# BontempoV2.net
KiCad netlist of a schematic drawn in EAGLE
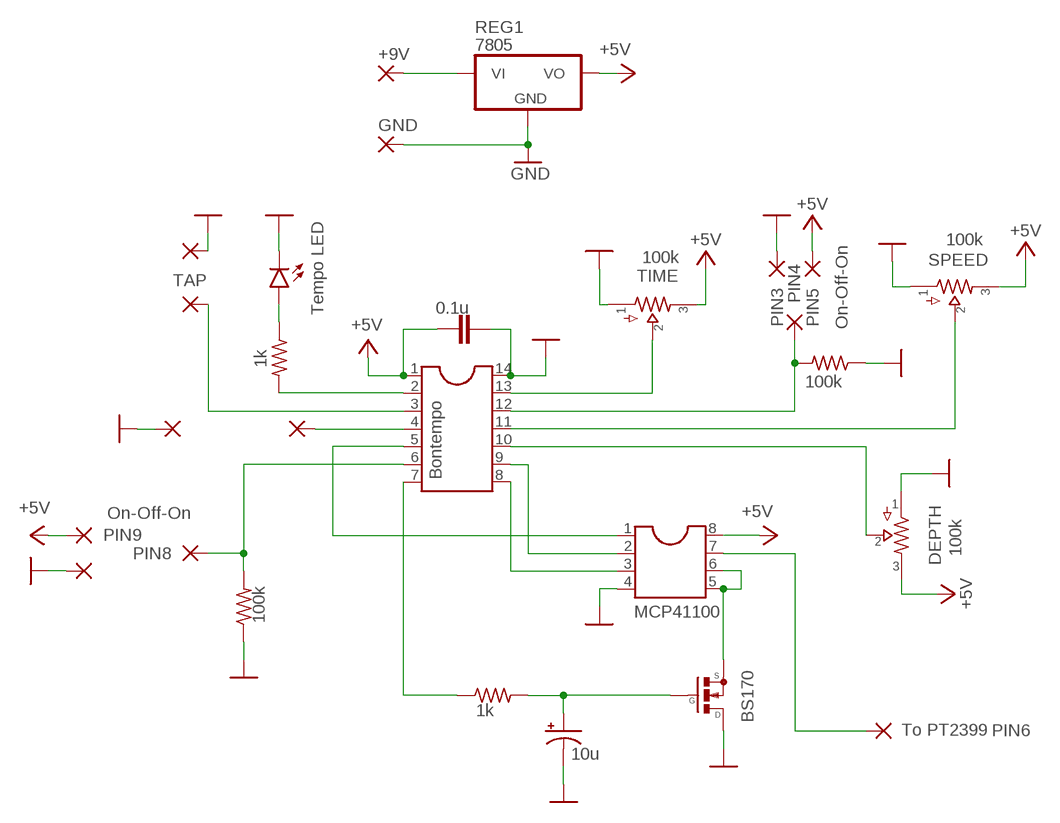
[diagram p0: schematic, sheet 1]

(export (version "E")
  (design (tool "Eeschema 10.0.6"))
  (components
    (comp (ref "+9V")
      (value "2,54/1,1")
      (footprint "eagle-import:2,54_1,1")
      (libsource (lib "eagle-import") (part "2,54/1,1"))
    )
    (comp (ref "C1")
      (value "10u")
      (footprint "eagle-import:050_020")
      (libsource (lib "eagle-import") (part "0500"))
    )
    (comp (ref "C2")
      (value "0.1u")
      (footprint "eagle-import:BOX_SMALL")
      (libsource (lib "eagle-import") (part "CER/FILMBOX.1"))
    )
    (comp (ref "D1")
      (value "LED3MM")
      (footprint "eagle-import:LED3MM")
      (libsource (lib "eagle-import") (part "LED3MM"))
    )
    (comp (ref "DEPTH")
      (value "100k")
      (footprint "eagle-import:PADS_SMALL")
      (libsource (lib "eagle-import") (part "POTSSMALL_PADS"))
    )
    (comp (ref "GND")
      (value "2,54/1,1")
      (footprint "eagle-import:2,54_1,1")
      (libsource (lib "eagle-import") (part "2,54/1,1"))
    )
    (comp (ref "IC1")
      (value "Bontempo")
      (footprint "eagle-import:DIL14")
      (libsource (lib "eagle-import") (part "DIL14"))
    )
    (comp (ref "IC2")
      (value "MCP41100")
      (footprint "eagle-import:DIL08")
      (libsource (lib "eagle-import") (part "DIL8"))
    )
    (comp (ref "PIN1")
      (value "2,54/1,1")
      (footprint "eagle-import:2,54_1,1")
      (libsource (lib "eagle-import") (part "2,54/1,1"))
    )
    (comp (ref "PIN2")
      (value "2,54/1,1")
      (footprint "eagle-import:2,54_1,1")
      (libsource (lib "eagle-import") (part "2,54/1,1"))
    )
    (comp (ref "PIN3")
      (value "2,54/1,1")
      (footprint "eagle-import:2,54_1,1")
      (libsource (lib "eagle-import") (part "2,54/1,1"))
    )
    (comp (ref "PIN4")
      (value "2,54/1,1")
      (footprint "eagle-import:2,54_1,1")
      (libsource (lib "eagle-import") (part "2,54/1,1"))
    )
    (comp (ref "PIN5")
      (value "2,54/1,1")
      (footprint "eagle-import:2,54_1,1")
      (libsource (lib "eagle-import") (part "2,54/1,1"))
    )
    (comp (ref "PIN6")
      (value "2,54/1,1")
      (footprint "eagle-import:2,54_1,1")
      (libsource (lib "eagle-import") (part "2,54/1,1"))
    )
    (comp (ref "PIN7")
      (value "2,54/1,1")
      (footprint "eagle-import:2,54_1,1")
      (libsource (lib "eagle-import") (part "2,54/1,1"))
    )
    (comp (ref "PIN8")
      (value "2,54/1,1")
      (footprint "eagle-import:2,54_1,1")
      (libsource (lib "eagle-import") (part "2,54/1,1"))
    )
    (comp (ref "PIN9")
      (value "2,54/1,1")
      (footprint "eagle-import:2,54_1,1")
      (libsource (lib "eagle-import") (part "2,54/1,1"))
    )
    (comp (ref "PIN11")
      (value "2,54/1,1")
      (footprint "eagle-import:2,54_1,1")
      (libsource (lib "eagle-import") (part "2,54/1,1"))
    )
    (comp (ref "PIN12")
      (value "2,54/1,1")
      (footprint "eagle-import:2,54_1,1")
      (libsource (lib "eagle-import") (part "2,54/1,1"))
    )
    (comp (ref "Q1")
      (value "BS170")
      (footprint "eagle-import:SOT54ES")
      (libsource (lib "eagle-import") (part "BS170"))
    )
    (comp (ref "R1")
      (value "1k")
      (footprint "eagle-import:R0207_3")
      (libsource (lib "eagle-import") (part "R_.3B"))
    )
    (comp (ref "R3")
      (value "1k")
      (footprint "eagle-import:R0207_3")
      (libsource (lib "eagle-import") (part "R_.3B"))
    )
    (comp (ref "R4")
      (value "100k")
      (footprint "eagle-import:R0207_3")
      (libsource (lib "eagle-import") (part "R_.3B"))
    )
    (comp (ref "R5")
      (value "100k")
      (footprint "eagle-import:R0207_3")
      (libsource (lib "eagle-import") (part "R_.3B"))
    )
    (comp (ref "REG1")
      (value "7805")
      (footprint "eagle-import:TO92-")
      (libsource (lib "eagle-import") (part "7805"))
    )
    (comp (ref "SPEED")
      (value "100k")
      (footprint "eagle-import:PADS_SMALL")
      (libsource (lib "eagle-import") (part "POTSSMALL_PADS"))
    )
    (comp (ref "TIME")
      (value "100k")
      (footprint "eagle-import:PADS_SMALL")
      (libsource (lib "eagle-import") (part "POTSSMALL_PADS"))
    )
  )
  (nets
    (net (code "1") (name "+5V") (class "Default")
      (node (ref "C2") (pin "1") (pinfunction "1_1") (pintype "passive"))
      (node (ref "DEPTH") (pin "3") (pinfunction "3_3") (pintype "passive"))
      (node (ref "IC1") (pin "1") (pinfunction "1_1") (pintype "passive"))
      (node (ref "IC2") (pin "8") (pinfunction "8_8") (pintype "passive"))
      (node (ref "PIN5") (pin "1") (pinfunction "P_1") (pintype "passive"))
      (node (ref "PIN9") (pin "1") (pinfunction "P_1") (pintype "passive"))
      (node (ref "REG1") (pin "3") (pinfunction "VO_3") (pintype "passive"))
      (node (ref "SPEED") (pin "3") (pinfunction "3_3") (pintype "passive"))
      (node (ref "TIME") (pin "3") (pinfunction "3_3") (pintype "passive"))
    )
    (net (code "2") (name "GND") (class "Default")
      (node (ref "C1") (pin "-") (pinfunction "-_-") (pintype "passive"))
      (node (ref "C2") (pin "2") (pinfunction "2_2") (pintype "passive"))
      (node (ref "D1") (pin "K") (pinfunction "C_K") (pintype "passive"))
      (node (ref "DEPTH") (pin "1") (pinfunction "1_1") (pintype "passive"))
      (node (ref "GND") (pin "1") (pinfunction "P_1") (pintype "passive"))
      (node (ref "IC1") (pin "14") (pinfunction "14_14") (pintype "passive"))
      (node (ref "IC2") (pin "4") (pinfunction "4_4") (pintype "passive"))
      (node (ref "PIN11") (pin "1") (pinfunction "P_1") (pintype "passive"))
      (node (ref "PIN2") (pin "1") (pinfunction "P_1") (pintype "passive"))
      (node (ref "PIN3") (pin "1") (pinfunction "P_1") (pintype "passive"))
      (node (ref "PIN7") (pin "1") (pinfunction "P_1") (pintype "passive"))
      (node (ref "Q1") (pin "D") (pinfunction "D_D") (pintype "passive"))
      (node (ref "R4") (pin "1") (pinfunction "1_1") (pintype "passive"))
      (node (ref "R5") (pin "1") (pinfunction "1_1") (pintype "passive"))
      (node (ref "REG1") (pin "2") (pinfunction "GND_2") (pintype "passive"))
      (node (ref "SPEED") (pin "1") (pinfunction "1_1") (pintype "passive"))
      (node (ref "TIME") (pin "1") (pinfunction "1_1") (pintype "passive"))
    )
    (net (code "3") (name "Net-(+9V-P)") (class "Default")
      (node (ref "+9V") (pin "1") (pinfunction "P_1") (pintype "passive"))
      (node (ref "REG1") (pin "1") (pinfunction "VI_1") (pintype "input"))
    )
    (net (code "4") (name "Net-(C1-Pad+)") (class "Default")
      (node (ref "C1") (pin "+") (pinfunction "+_+") (pintype "passive"))
      (node (ref "Q1") (pin "G") (pinfunction "G_G") (pintype "passive"))
      (node (ref "R3") (pin "2") (pinfunction "2_2") (pintype "passive"))
    )
    (net (code "5") (name "Net-(D1-PadA)") (class "Default")
      (node (ref "D1") (pin "A") (pinfunction "A_A") (pintype "passive"))
      (node (ref "R1") (pin "1") (pinfunction "1_1") (pintype "passive"))
    )
    (net (code "6") (name "Net-(DEPTH-Pad2)") (class "Default")
      (node (ref "DEPTH") (pin "2") (pinfunction "2_2") (pintype "passive"))
      (node (ref "IC1") (pin "10") (pinfunction "10_10") (pintype "passive"))
    )
    (net (code "7") (name "Net-(IC1-Pad2)") (class "Default")
      (node (ref "IC1") (pin "2") (pinfunction "2_2") (pintype "passive"))
      (node (ref "R1") (pin "2") (pinfunction "2_2") (pintype "passive"))
    )
    (net (code "8") (name "Net-(IC1-Pad5)") (class "Default")
      (node (ref "IC1") (pin "5") (pinfunction "5_5") (pintype "passive"))
      (node (ref "IC2") (pin "1") (pinfunction "1_1") (pintype "passive"))
    )
    (net (code "9") (name "Net-(IC1-Pad7)") (class "Default")
      (node (ref "IC1") (pin "7") (pinfunction "7_7") (pintype "passive"))
      (node (ref "R3") (pin "1") (pinfunction "1_1") (pintype "passive"))
    )
    (net (code "10") (name "Net-(IC1-Pad8)") (class "Default")
      (node (ref "IC1") (pin "8") (pinfunction "8_8") (pintype "passive"))
      (node (ref "IC2") (pin "3") (pinfunction "3_3") (pintype "passive"))
    )
    (net (code "11") (name "Net-(IC1-Pad9)") (class "Default")
      (node (ref "IC1") (pin "9") (pinfunction "9_9") (pintype "passive"))
      (node (ref "IC2") (pin "2") (pinfunction "2_2") (pintype "passive"))
    )
    (net (code "12") (name "Net-(IC1-Pad11)") (class "Default")
      (node (ref "IC1") (pin "11") (pinfunction "11_11") (pintype "passive"))
      (node (ref "SPEED") (pin "2") (pinfunction "2_2") (pintype "passive"))
    )
    (net (code "13") (name "Net-(IC1-Pad13)") (class "Default")
      (node (ref "IC1") (pin "13") (pinfunction "13_13") (pintype "passive"))
      (node (ref "TIME") (pin "2") (pinfunction "2_2") (pintype "passive"))
    )
    (net (code "14") (name "Net-(IC2-Pad5)") (class "Default")
      (node (ref "IC2") (pin "5") (pinfunction "5_5") (pintype "passive"))
      (node (ref "IC2") (pin "6") (pinfunction "6_6") (pintype "passive"))
      (node (ref "Q1") (pin "S") (pinfunction "S_S") (pintype "passive"))
    )
    (net (code "15") (name "Net-(PIN1-P)") (class "Default")
      (node (ref "IC1") (pin "3") (pinfunction "3_3") (pintype "passive"))
      (node (ref "PIN1") (pin "1") (pinfunction "P_1") (pintype "passive"))
    )
    (net (code "16") (name "Net-(PIN4-P)") (class "Default")
      (node (ref "IC1") (pin "12") (pinfunction "12_12") (pintype "passive"))
      (node (ref "PIN4") (pin "1") (pinfunction "P_1") (pintype "passive"))
      (node (ref "R5") (pin "2") (pinfunction "2_2") (pintype "passive"))
    )
    (net (code "17") (name "Net-(PIN6-P)") (class "Default")
      (node (ref "IC2") (pin "7") (pinfunction "7_7") (pintype "passive"))
      (node (ref "PIN6") (pin "1") (pinfunction "P_1") (pintype "passive"))
    )
    (net (code "18") (name "Net-(PIN8-P)") (class "Default")
      (node (ref "IC1") (pin "6") (pinfunction "6_6") (pintype "passive"))
      (node (ref "PIN8") (pin "1") (pinfunction "P_1") (pintype "passive"))
      (node (ref "R4") (pin "2") (pinfunction "2_2") (pintype "passive"))
    )
    (net (code "19") (name "Net-(PIN12-P)") (class "Default")
      (node (ref "IC1") (pin "4") (pinfunction "4_4") (pintype "passive"))
      (node (ref "PIN12") (pin "1") (pinfunction "P_1") (pintype "passive"))
    )
  )
)
